# 02_-_USB.net
KiCad netlist of a schematic drawn in Altium Designer
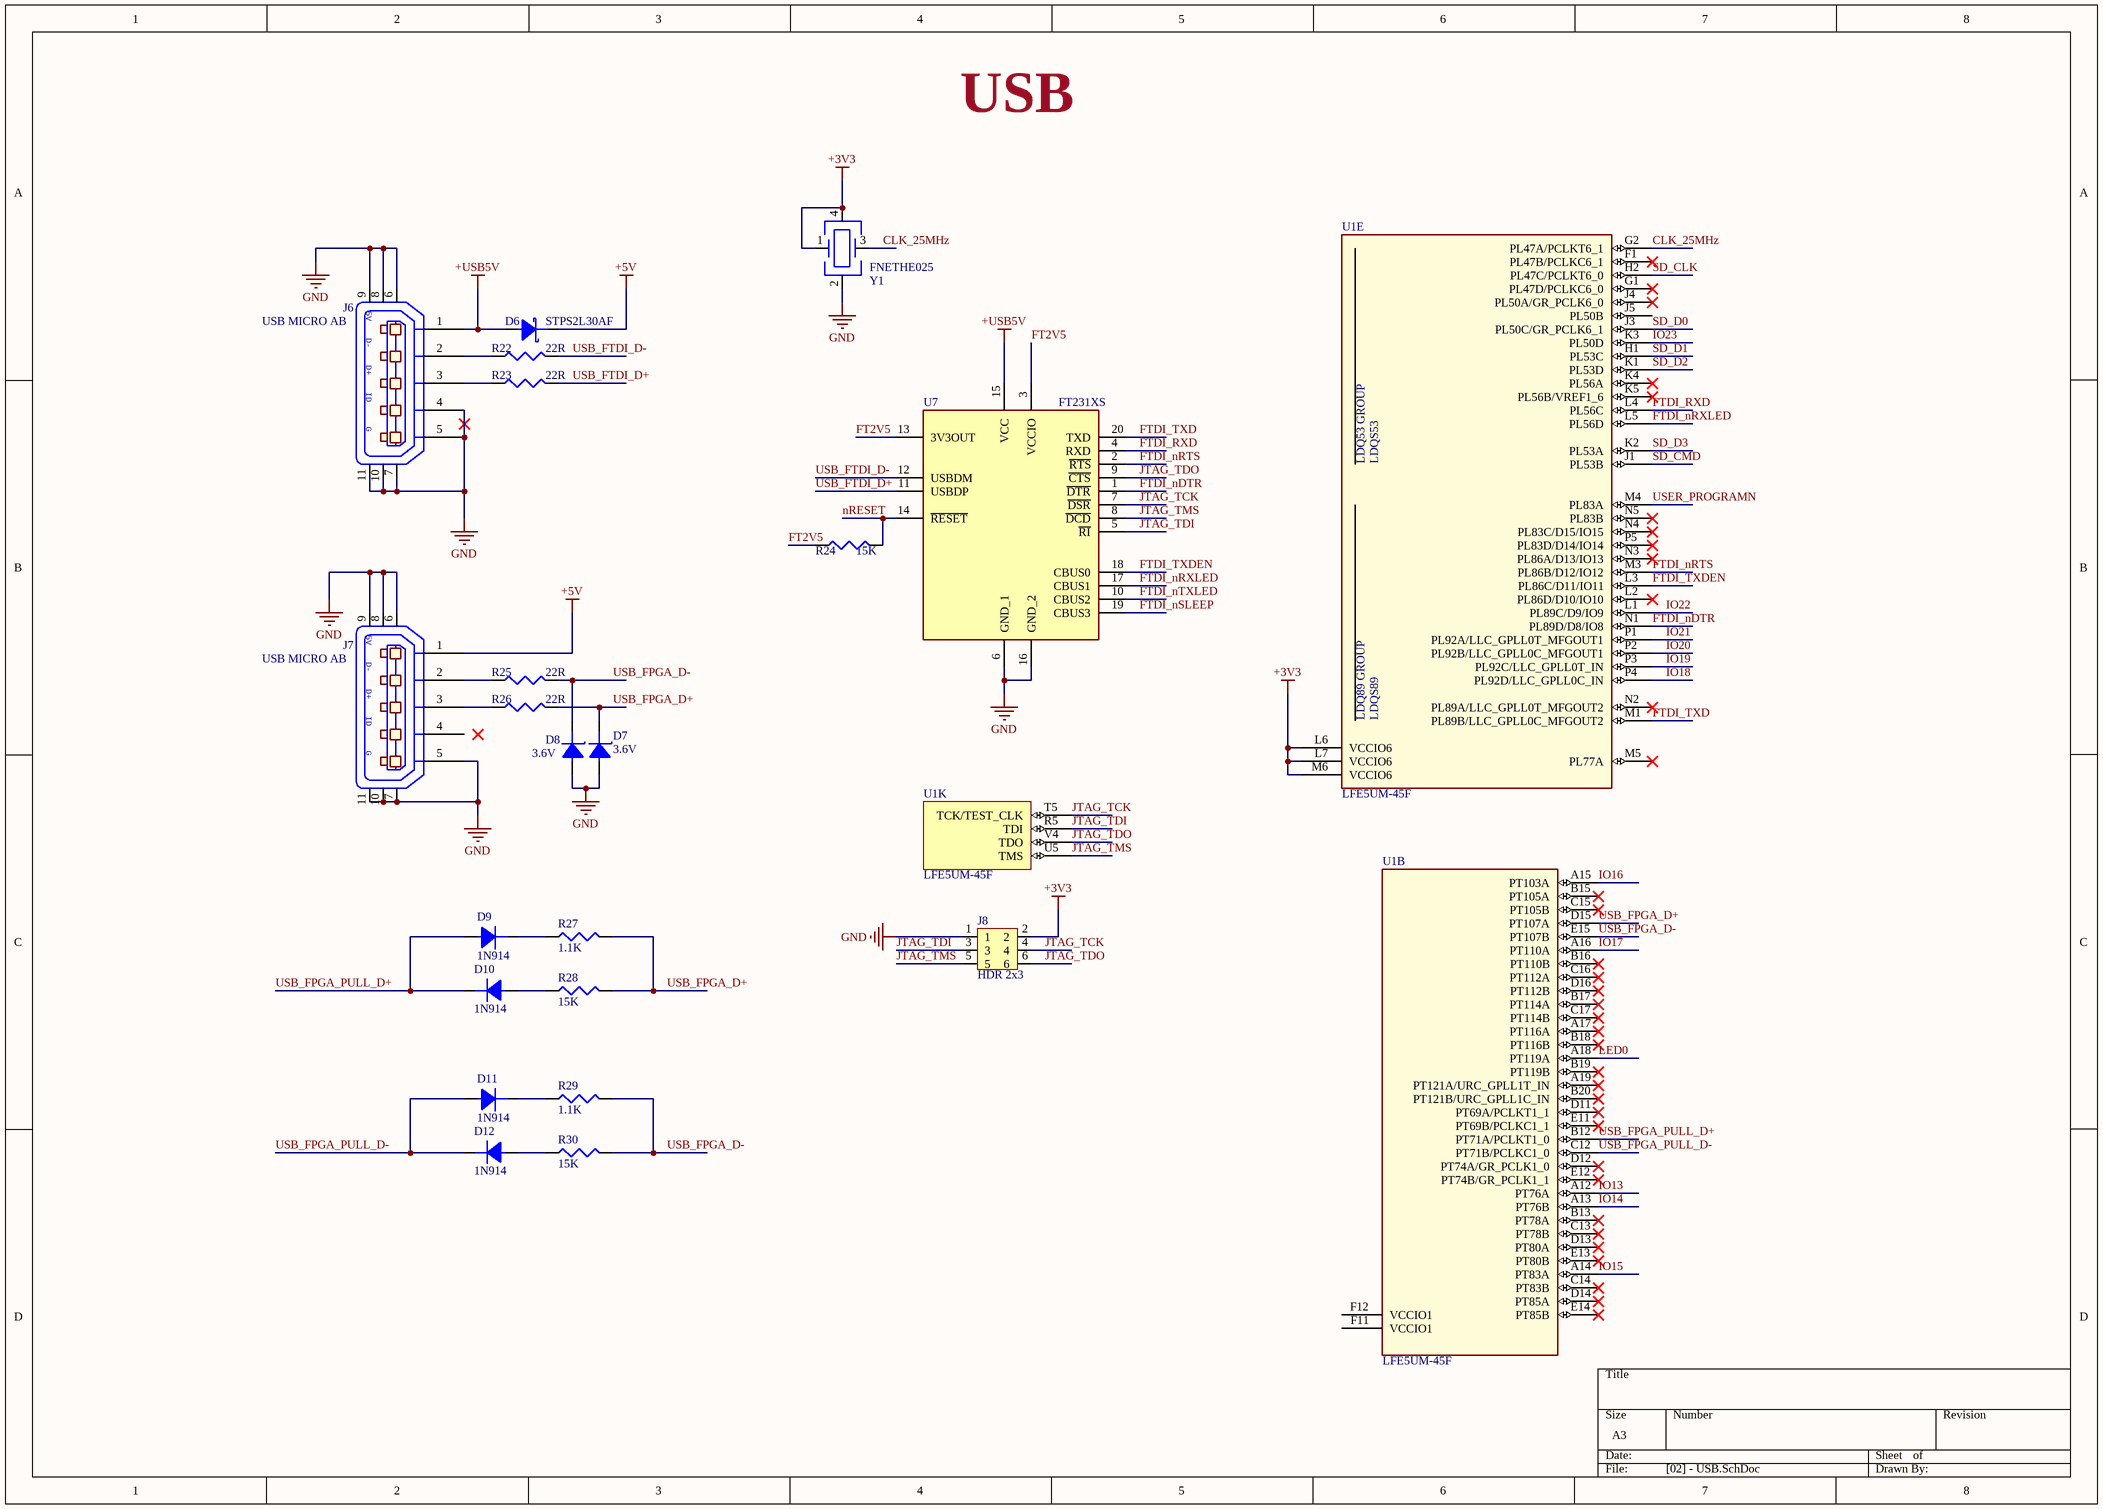
[diagram p0: [02] - USB.SchDoc]

(export (version "E")
  (design (tool "Eeschema 10.0.6"))
  (components
    (comp (ref "D6")
      (value "STPS2L30AF")
      (footprint "SMA")
      (description "DIODE SCHOTTKY 30V 2A SMA")
      (fields (field (name "MANUFACTURER") "STMicroelectronics"))
      (libsource (lib "ECP5_V2") (part "STPS2L30AF"))
    )
    (comp (ref "D7")
      (value "3.6V")
      (footprint "SOD323")
      (description "Diode Zener Single 3.6V 5% 200mW 2-Pin SOD-323 T/R")
      (fields (field (name "MANUFACTURER") "MCC") (field (name "MANUFACTURER PART NUMBER") "BZT52C3V6S-TP"))
      (libsource (lib "ECP5_V2") (part "BZT52C3V6S-TP"))
    )
    (comp (ref "D8")
      (value "3.6V")
      (footprint "SOD323")
      (description "Diode Zener Single 3.6V 5% 200mW 2-Pin SOD-323 T/R")
      (fields (field (name "MANUFACTURER") "MCC") (field (name "MANUFACTURER PART NUMBER") "BZT52C3V6S-TP"))
      (libsource (lib "ECP5_V2") (part "BZT52C3V6S-TP"))
    )
    (comp (ref "D9")
      (value "1N914")
      (footprint "SOD323")
      (description "ON SEMICONDUCTOR/FAIRCHILD - 1N914BWS. - SMALL SIGNAL DIODE")
      (fields
        (field (name "MANUFACTURER") "ON Semiconductor / Fairchild")
        (field (name "MANUFACTURER PART NUMBER") "1N914BWS")
      )
      (libsource (lib "ECP5_V2") (part "1N914BWS"))
    )
    (comp (ref "D10")
      (value "1N914")
      (footprint "SOD323")
      (description "ON SEMICONDUCTOR/FAIRCHILD - 1N914BWS. - SMALL SIGNAL DIODE")
      (fields
        (field (name "MANUFACTURER") "ON Semiconductor / Fairchild")
        (field (name "MANUFACTURER PART NUMBER") "1N914BWS")
      )
      (libsource (lib "ECP5_V2") (part "1N914BWS"))
    )
    (comp (ref "D11")
      (value "1N914")
      (footprint "SOD323")
      (description "ON SEMICONDUCTOR/FAIRCHILD - 1N914BWS. - SMALL SIGNAL DIODE")
      (fields
        (field (name "MANUFACTURER") "ON Semiconductor / Fairchild")
        (field (name "MANUFACTURER PART NUMBER") "1N914BWS")
      )
      (libsource (lib "ECP5_V2") (part "1N914BWS"))
    )
    (comp (ref "D12")
      (value "1N914")
      (footprint "SOD323")
      (description "ON SEMICONDUCTOR/FAIRCHILD - 1N914BWS. - SMALL SIGNAL DIODE")
      (fields
        (field (name "MANUFACTURER") "ON Semiconductor / Fairchild")
        (field (name "MANUFACTURER PART NUMBER") "1N914BWS")
      )
      (libsource (lib "ECP5_V2") (part "1N914BWS"))
    )
    (comp (ref "J6")
      (value "USB MICRO AB")
      (footprint "USB_Micro_AB")
      (description "CONN RCPT MICRO USB AB R/A SMD")
      (fields
        (field (name "MANUFACTURER") "Molex Inc")
        (field (name "MANUFACTURER PART NUMBER") "0475890001")
        (field (name ".CREATOR") "MM")
        (field (name ".CHECKED PCB") "MM")
        (field (name ".CHECKED SCH") "MM")
      )
      (libsource (lib "ECP5_V2") (part "0475890001"))
    )
    (comp (ref "J7")
      (value "USB MICRO AB")
      (footprint "USB_Micro_AB")
      (description "CONN RCPT MICRO USB AB R/A SMD")
      (fields
        (field (name "MANUFACTURER") "Molex Inc")
        (field (name "MANUFACTURER PART NUMBER") "0475890001")
        (field (name ".CREATOR") "MM")
        (field (name ".CHECKED PCB") "MM")
        (field (name ".CHECKED SCH") "MM")
      )
      (libsource (lib "ECP5_V2") (part "0475890001"))
    )
    (comp (ref "J8")
      (value "HDR 2x3")
      (footprint "HDR_2x3_2.54MM")
      (description "CONN HEADER VERT 6POS 2.54MM")
      (fields
        (field (name "MANUFACTURER") "Amphenol FCI")
        (field (name "MANUFACTURER PART NUMBER") "67997-106HLF")
      )
      (libsource (lib "ECP5_V2") (part "67997-106HLF"))
    )
    (comp (ref "R22")
      (value "22R")
      (footprint "R0603")
      (description "Res Thick Film 0603 22 Ohm 1% 0.1W(1/10W) ±100ppm/C Pad SMD T/R")
      (fields
        (field (name "MANUFACTURER") "Yageo")
        (field (name "MANUFACTURER PART NUMBER") "RC0603FR-0722RL")
      )
      (libsource (lib "ECP5_V2") (part "RC0603FR-0722RL"))
    )
    (comp (ref "R23")
      (value "22R")
      (footprint "R0603")
      (description "Res Thick Film 0603 22 Ohm 1% 0.1W(1/10W) ±100ppm/C Pad SMD T/R")
      (fields
        (field (name "MANUFACTURER") "Yageo")
        (field (name "MANUFACTURER PART NUMBER") "RC0603FR-0722RL")
      )
      (libsource (lib "ECP5_V2") (part "RC0603FR-0722RL"))
    )
    (comp (ref "R24")
      (value "15K")
      (footprint "R0603")
      (description "Res Thick Film 0603 15K Ohm 1% 1/10W ?100ppm/?C Molded SMD Paper T/R")
      (fields
        (field (name "MANUFACTURER") "Yageo")
        (field (name "MANUFACTURER PART NUMBER") "RC0603FR-0715KL")
      )
      (libsource (lib "ECP5_V2") (part "RC0603FR-0715KL"))
    )
    (comp (ref "R25")
      (value "22R")
      (footprint "R0603")
      (description "Res Thick Film 0603 22 Ohm 1% 0.1W(1/10W) ±100ppm/C Pad SMD T/R")
      (fields
        (field (name "MANUFACTURER") "Yageo")
        (field (name "MANUFACTURER PART NUMBER") "RC0603FR-0722RL")
      )
      (libsource (lib "ECP5_V2") (part "RC0603FR-0722RL"))
    )
    (comp (ref "R26")
      (value "22R")
      (footprint "R0603")
      (description "Res Thick Film 0603 22 Ohm 1% 0.1W(1/10W) ±100ppm/C Pad SMD T/R")
      (fields
        (field (name "MANUFACTURER") "Yageo")
        (field (name "MANUFACTURER PART NUMBER") "RC0603FR-0722RL")
      )
      (libsource (lib "ECP5_V2") (part "RC0603FR-0722RL"))
    )
    (comp (ref "R27")
      (value "1.1K")
      (footprint "R0603")
      (description "RES SMD 1.1K OHM 1% 1/10W 0603")
      (fields
        (field (name "MANUFACTURER") "Yageo")
        (field (name "MANUFACTURER PART NUMBER") "RC0603FR-071K1L")
      )
      (libsource (lib "ECP5_V2") (part "RC0603FR-071K1L"))
    )
    (comp (ref "R28")
      (value "15K")
      (footprint "R0603")
      (description "Res Thick Film 0603 15K Ohm 1% 1/10W ?100ppm/?C Molded SMD Paper T/R")
      (fields
        (field (name "MANUFACTURER") "Yageo")
        (field (name "MANUFACTURER PART NUMBER") "RC0603FR-0715KL")
      )
      (libsource (lib "ECP5_V2") (part "RC0603FR-0715KL"))
    )
    (comp (ref "R29")
      (value "1.1K")
      (footprint "R0603")
      (description "RES SMD 1.1K OHM 1% 1/10W 0603")
      (fields
        (field (name "MANUFACTURER") "Yageo")
        (field (name "MANUFACTURER PART NUMBER") "RC0603FR-071K1L")
      )
      (libsource (lib "ECP5_V2") (part "RC0603FR-071K1L"))
    )
    (comp (ref "R30")
      (value "15K")
      (footprint "R0603")
      (description "Res Thick Film 0603 15K Ohm 1% 1/10W ?100ppm/?C Molded SMD Paper T/R")
      (fields
        (field (name "MANUFACTURER") "Yageo")
        (field (name "MANUFACTURER PART NUMBER") "RC0603FR-0715KL")
      )
      (libsource (lib "ECP5_V2") (part "RC0603FR-0715KL"))
    )
    (comp (ref "U1")
      (value "LFE5UM-45F")
      (footprint "LFE5BG381")
      (description "ECP5 Series 44 K LUTs 203 I/O 1.1 V Slow Surface Mount FPGA - CABGA-381")
      (fields
        (field (name "MANUFACTURER") "Lattice Semiconductor")
        (field (name "MANUFACTURER PART NUMBER") "LFE5UM-45F-6BG381C")
      )
      (libsource (lib "ECP5_V2") (part "LFE5UM-45F-6BG381C"))
    )
    (comp (ref "U7")
      (value "FT231XS")
      (footprint "SOP64P599X175-20N")
      (fields (field (name "MANUFACTURER") "FTDI") (field (name "MANUFACTURER PART NUMBER") "FT231XS-R"))
      (libsource (lib "ECP5_V2") (part "FT231XS-R"))
    )
    (comp (ref "Y1")
      (value "FNETHE025")
      (footprint "TSOP440P690X140-4N")
      (description "SMD Crystal Oscillator 25MHz 3.3V 15pF 4-Pin CSMD")
      (fields (field (name "MANUFACTURER") "Diodes"))
      (libsource (lib "ECP5_V2") (part "FNETHE025"))
    )
  )
  (nets
    (net (code "1") (name "+3V3") (class "Default")
      (node (ref "J8") (pin "2") (pinfunction "2_2") (pintype "passive"))
      (node (ref "U1") (pin "L6") (pinfunction "VCCIO6_L6") (pintype "power_in"))
      (node (ref "U1") (pin "L7") (pinfunction "VCCIO6_L7") (pintype "power_in"))
      (node (ref "U1") (pin "M6") (pinfunction "VCCIO6_M6") (pintype "power_in"))
      (node (ref "Y1") (pin "1") (pintype "passive"))
      (node (ref "Y1") (pin "4") (pinfunction "4_4") (pintype "passive"))
    )
    (net (code "2") (name "+5V") (class "Default")
      (node (ref "D6") (pin "1") (pinfunction "Cathode_1") (pintype "passive"))
      (node (ref "J7") (pin "1") (pinfunction "P1_1") (pintype "passive"))
    )
    (net (code "3") (name "+USB5V") (class "Default")
      (node (ref "D6") (pin "2") (pinfunction "Anode_2") (pintype "passive"))
      (node (ref "J6") (pin "1") (pinfunction "P1_1") (pintype "passive"))
      (node (ref "U7") (pin "15") (pinfunction "VCC_15") (pintype "passive"))
    )
    (net (code "4") (name "/CLK_25MHz") (class "Default")
      (node (ref "U1") (pin "G2") (pinfunction "PL47A/PCLKT6_1_G2") (pintype "bidirectional"))
      (node (ref "Y1") (pin "3") (pinfunction "3_3") (pintype "passive"))
    )
    (net (code "5") (name "/FT2V5") (class "Default")
      (node (ref "R24") (pin "1") (pinfunction "1_1") (pintype "passive"))
      (node (ref "U7") (pin "13") (pinfunction "3V3OUT_13") (pintype "passive"))
      (node (ref "U7") (pin "3") (pinfunction "VCCIO_3") (pintype "passive"))
    )
    (net (code "6") (name "/FTDI_RXD") (class "Default")
      (node (ref "U1") (pin "L4") (pinfunction "PL56C_L4") (pintype "bidirectional"))
      (node (ref "U7") (pin "4") (pinfunction "RXD_4") (pintype "passive"))
    )
    (net (code "7") (name "/FTDI_TXD") (class "Default")
      (node (ref "U1") (pin "M1") (pinfunction "PL89B/LLC_GPLL0C_MFGOUT2_M1") (pintype "bidirectional"))
      (node (ref "U7") (pin "20") (pinfunction "TXD_20") (pintype "passive"))
    )
    (net (code "8") (name "/FTDI_TXDEN") (class "Default")
      (node (ref "U1") (pin "L3") (pinfunction "PL86C/D11/IO11_L3") (pintype "bidirectional"))
      (node (ref "U7") (pin "18") (pinfunction "CBUS0_18") (pintype "passive"))
    )
    (net (code "9") (name "/FTDI_nDTR") (class "Default")
      (node (ref "U1") (pin "N1") (pinfunction "PL89D/D8/IO8_N1") (pintype "bidirectional"))
      (node (ref "U7") (pin "1") (pinfunction "~{DTR}_1") (pintype "passive"))
    )
    (net (code "10") (name "/FTDI_nRTS") (class "Default")
      (node (ref "U1") (pin "M3") (pinfunction "PL86B/D12/IO12_M3") (pintype "bidirectional"))
      (node (ref "U7") (pin "2") (pinfunction "~{RTS}_2") (pintype "passive"))
    )
    (net (code "11") (name "/FTDI_nRXLED") (class "Default")
      (node (ref "U1") (pin "L5") (pinfunction "PL56D_L5") (pintype "bidirectional"))
      (node (ref "U7") (pin "17") (pinfunction "CBUS1_17") (pintype "passive"))
    )
    (net (code "12") (name "/FTDI_nSLEEP") (class "Default")
      (node (ref "U7") (pin "19") (pinfunction "CBUS3_19") (pintype "passive"))
    )
    (net (code "13") (name "/FTDI_nTXLED") (class "Default")
      (node (ref "U7") (pin "10") (pinfunction "CBUS2_10") (pintype "passive"))
    )
    (net (code "14") (name "/IO13") (class "Default")
      (node (ref "U1") (pin "A12") (pinfunction "PT76A_A12") (pintype "bidirectional"))
    )
    (net (code "15") (name "/IO14") (class "Default")
      (node (ref "U1") (pin "A13") (pinfunction "PT76B_A13") (pintype "bidirectional"))
    )
    (net (code "16") (name "/IO15") (class "Default")
      (node (ref "U1") (pin "A14") (pinfunction "PT83A_A14") (pintype "bidirectional"))
    )
    (net (code "17") (name "/IO16") (class "Default")
      (node (ref "U1") (pin "A15") (pinfunction "PT103A_A15") (pintype "bidirectional"))
    )
    (net (code "18") (name "/IO17") (class "Default")
      (node (ref "U1") (pin "A16") (pinfunction "PT110A_A16") (pintype "bidirectional"))
    )
    (net (code "19") (name "/IO18") (class "Default")
      (node (ref "U1") (pin "P4") (pinfunction "PL92D/LLC_GPLL0C_IN_P4") (pintype "bidirectional"))
    )
    (net (code "20") (name "/IO19") (class "Default")
      (node (ref "U1") (pin "P3") (pinfunction "PL92C/LLC_GPLL0T_IN_P3") (pintype "bidirectional"))
    )
    (net (code "21") (name "/IO20") (class "Default")
      (node (ref "U1") (pin "P2") (pinfunction "PL92B/LLC_GPLL0C_MFGOUT1_P2") (pintype "bidirectional"))
    )
    (net (code "22") (name "/IO21") (class "Default")
      (node (ref "U1") (pin "P1") (pinfunction "PL92A/LLC_GPLL0T_MFGOUT1_P1") (pintype "bidirectional"))
    )
    (net (code "23") (name "/IO22") (class "Default")
      (node (ref "U1") (pin "L1") (pinfunction "PL89C/D9/IO9_L1") (pintype "bidirectional"))
    )
    (net (code "24") (name "/IO23") (class "Default")
      (node (ref "U1") (pin "K3") (pinfunction "PL50D_K3") (pintype "bidirectional"))
    )
    (net (code "25") (name "/JTAG_TCK") (class "Default")
      (node (ref "J8") (pin "4") (pinfunction "4_4") (pintype "passive"))
      (node (ref "U1") (pin "T5") (pinfunction "TCK/TEST_CLK_T5") (pintype "bidirectional"))
      (node (ref "U7") (pin "7") (pinfunction "~{DSR}_7") (pintype "passive"))
    )
    (net (code "26") (name "/JTAG_TDI") (class "Default")
      (node (ref "J8") (pin "3") (pinfunction "3_3") (pintype "passive"))
      (node (ref "U1") (pin "R5") (pinfunction "TDI_R5") (pintype "bidirectional"))
      (node (ref "U7") (pin "5") (pinfunction "~{RI}_5") (pintype "passive"))
    )
    (net (code "27") (name "/JTAG_TDO") (class "Default")
      (node (ref "J8") (pin "6") (pinfunction "6_6") (pintype "passive"))
      (node (ref "U1") (pin "V4") (pinfunction "TDO_V4") (pintype "bidirectional"))
      (node (ref "U7") (pin "9") (pinfunction "~{CTS}_9") (pintype "passive"))
    )
    (net (code "28") (name "/JTAG_TMS") (class "Default")
      (node (ref "J8") (pin "5") (pinfunction "5_5") (pintype "passive"))
      (node (ref "U1") (pin "U5") (pinfunction "TMS_U5") (pintype "bidirectional"))
      (node (ref "U7") (pin "8") (pinfunction "~{DCD}_8") (pintype "passive"))
    )
    (net (code "29") (name "/LED0") (class "Default")
      (node (ref "U1") (pin "A18") (pinfunction "PT119A_A18") (pintype "bidirectional"))
    )
    (net (code "30") (name "/SD_CLK") (class "Default")
      (node (ref "U1") (pin "H2") (pinfunction "PL47C/PCLKT6_0_H2") (pintype "bidirectional"))
    )
    (net (code "31") (name "/SD_CMD") (class "Default")
      (node (ref "U1") (pin "J1") (pinfunction "PL53B_J1") (pintype "bidirectional"))
    )
    (net (code "32") (name "/SD_D0") (class "Default")
      (node (ref "U1") (pin "J3") (pinfunction "PL50C/GR_PCLK6_1_J3") (pintype "bidirectional"))
    )
    (net (code "33") (name "/SD_D1") (class "Default")
      (node (ref "U1") (pin "H1") (pinfunction "PL53C_H1") (pintype "bidirectional"))
    )
    (net (code "34") (name "/SD_D2") (class "Default")
      (node (ref "U1") (pin "K1") (pinfunction "PL53D_K1") (pintype "bidirectional"))
    )
    (net (code "35") (name "/SD_D3") (class "Default")
      (node (ref "U1") (pin "K2") (pinfunction "PL53A_K2") (pintype "bidirectional"))
    )
    (net (code "36") (name "/USB_FPGA_D+") (class "Default")
      (node (ref "D7") (pin "1") (pinfunction "Cathode_1") (pintype "passive"))
      (node (ref "R26") (pin "2") (pinfunction "2_2") (pintype "passive"))
      (node (ref "R27") (pin "2") (pinfunction "2_2") (pintype "passive"))
      (node (ref "R28") (pin "2") (pinfunction "2_2") (pintype "passive"))
      (node (ref "U1") (pin "D15") (pinfunction "PT107A_D15") (pintype "bidirectional"))
    )
    (net (code "37") (name "/USB_FPGA_D-") (class "Default")
      (node (ref "D8") (pin "1") (pinfunction "Cathode_1") (pintype "passive"))
      (node (ref "R25") (pin "2") (pinfunction "2_2") (pintype "passive"))
      (node (ref "R29") (pin "2") (pinfunction "2_2") (pintype "passive"))
      (node (ref "R30") (pin "2") (pinfunction "2_2") (pintype "passive"))
      (node (ref "U1") (pin "E15") (pinfunction "PT107B_E15") (pintype "bidirectional"))
    )
    (net (code "38") (name "/USB_FPGA_PULL_D+") (class "Default")
      (node (ref "D10") (pin "1") (pinfunction "Cathode_1") (pintype "passive"))
      (node (ref "D9") (pin "2") (pinfunction "Anode_2") (pintype "passive"))
      (node (ref "U1") (pin "B12") (pinfunction "PT71A/PCLKT1_0_B12") (pintype "bidirectional"))
    )
    (net (code "39") (name "/USB_FPGA_PULL_D-") (class "Default")
      (node (ref "D11") (pin "2") (pinfunction "Anode_2") (pintype "passive"))
      (node (ref "D12") (pin "1") (pinfunction "Cathode_1") (pintype "passive"))
      (node (ref "U1") (pin "C12") (pinfunction "PT71B/PCLKC1_0_C12") (pintype "bidirectional"))
    )
    (net (code "40") (name "/USB_FTDI_D+") (class "Default")
      (node (ref "R23") (pin "2") (pinfunction "2_2") (pintype "passive"))
      (node (ref "U7") (pin "11") (pinfunction "USBDP_11") (pintype "passive"))
    )
    (net (code "41") (name "/USB_FTDI_D-") (class "Default")
      (node (ref "R22") (pin "2") (pinfunction "2_2") (pintype "passive"))
      (node (ref "U7") (pin "12") (pinfunction "USBDM_12") (pintype "passive"))
    )
    (net (code "42") (name "/USER_PROGRAMN") (class "Default")
      (node (ref "U1") (pin "M4") (pinfunction "PL83A_M4") (pintype "bidirectional"))
    )
    (net (code "43") (name "/nRESET") (class "Default")
      (node (ref "R24") (pin "2") (pinfunction "2_2") (pintype "passive"))
      (node (ref "U7") (pin "14") (pinfunction "~{RESET}_14") (pintype "passive"))
    )
    (net (code "44") (name "GND") (class "Default")
      (node (ref "D7") (pin "2") (pinfunction "Anode_2") (pintype "passive"))
      (node (ref "D8") (pin "2") (pinfunction "Anode_2") (pintype "passive"))
      (node (ref "J6") (pin "10") (pinfunction "10_10") (pintype "passive"))
      (node (ref "J6") (pin "11") (pinfunction "11_11") (pintype "passive"))
      (node (ref "J6") (pin "4") (pinfunction "P4_4") (pintype "passive"))
      (node (ref "J6") (pin "5") (pinfunction "P5_5") (pintype "passive"))
      (node (ref "J6") (pin "6") (pinfunction "6_6") (pintype "passive"))
      (node (ref "J6") (pin "7") (pinfunction "7_7") (pintype "passive"))
      (node (ref "J6") (pin "8") (pinfunction "8_8") (pintype "passive"))
      (node (ref "J6") (pin "9") (pinfunction "9_9") (pintype "passive"))
      (node (ref "J7") (pin "10") (pinfunction "10_10") (pintype "passive"))
      (node (ref "J7") (pin "11") (pinfunction "11_11") (pintype "passive"))
      (node (ref "J7") (pin "5") (pinfunction "P5_5") (pintype "passive"))
      (node (ref "J7") (pin "6") (pinfunction "6_6") (pintype "passive"))
      (node (ref "J7") (pin "7") (pinfunction "7_7") (pintype "passive"))
      (node (ref "J7") (pin "8") (pinfunction "8_8") (pintype "passive"))
      (node (ref "J7") (pin "9") (pinfunction "9_9") (pintype "passive"))
      (node (ref "J8") (pin "1") (pinfunction "1_1") (pintype "passive"))
      (node (ref "U7") (pin "16") (pinfunction "GND_2_16") (pintype "passive"))
      (node (ref "U7") (pin "6") (pinfunction "GND_1_6") (pintype "passive"))
      (node (ref "Y1") (pin "2") (pinfunction "2_2") (pintype "passive"))
    )
    (net (code "45") (name "Net-(D9-Cathode)") (class "Default")
      (node (ref "D9") (pin "1") (pinfunction "Cathode_1") (pintype "passive"))
      (node (ref "R27") (pin "1") (pinfunction "1_1") (pintype "passive"))
    )
    (net (code "46") (name "Net-(D10-Anode)") (class "Default")
      (node (ref "D10") (pin "2") (pinfunction "Anode_2") (pintype "passive"))
      (node (ref "R28") (pin "1") (pinfunction "1_1") (pintype "passive"))
    )
    (net (code "47") (name "Net-(D11-Cathode)") (class "Default")
      (node (ref "D11") (pin "1") (pinfunction "Cathode_1") (pintype "passive"))
      (node (ref "R29") (pin "1") (pinfunction "1_1") (pintype "passive"))
    )
    (net (code "48") (name "Net-(D12-Anode)") (class "Default")
      (node (ref "D12") (pin "2") (pinfunction "Anode_2") (pintype "passive"))
      (node (ref "R30") (pin "1") (pinfunction "1_1") (pintype "passive"))
    )
    (net (code "49") (name "Net-(J6-P2)") (class "Default")
      (node (ref "J6") (pin "2") (pinfunction "P2_2") (pintype "passive"))
      (node (ref "R22") (pin "1") (pinfunction "1_1") (pintype "passive"))
    )
    (net (code "50") (name "Net-(J6-P3)") (class "Default")
      (node (ref "J6") (pin "3") (pinfunction "P3_3") (pintype "passive"))
      (node (ref "R23") (pin "1") (pinfunction "1_1") (pintype "passive"))
    )
    (net (code "51") (name "Net-(J7-P2)") (class "Default")
      (node (ref "J7") (pin "2") (pinfunction "P2_2") (pintype "passive"))
      (node (ref "R25") (pin "1") (pinfunction "1_1") (pintype "passive"))
    )
    (net (code "52") (name "Net-(J7-P3)") (class "Default")
      (node (ref "J7") (pin "3") (pinfunction "P3_3") (pintype "passive"))
      (node (ref "R26") (pin "1") (pinfunction "1_1") (pintype "passive"))
    )
    (net (code "53") (name "unconnected-(J7-P4-Pad4)") (class "Default")
      (node (ref "J7") (pin "4") (pinfunction "P4_4") (pintype "passive"))
    )
    (net (code "54") (name "unconnected-(U1B-PT69A{slash}PCLKT1_1-PadD11)") (class "Default")
      (node (ref "U1") (pin "D11") (pinfunction "PT69A/PCLKT1_1_D11") (pintype "bidirectional+no_connect"))
    )
    (net (code "55") (name "unconnected-(U1B-PT69B{slash}PCLKC1_1-PadE11)") (class "Default")
      (node (ref "U1") (pin "E11") (pinfunction "PT69B/PCLKC1_1_E11") (pintype "bidirectional+no_connect"))
    )
    (net (code "56") (name "unconnected-(U1B-PT74A{slash}GR_PCLK1_0-PadD12)") (class "Default")
      (node (ref "U1") (pin "D12") (pinfunction "PT74A/GR_PCLK1_0_D12") (pintype "bidirectional+no_connect"))
    )
    (net (code "57") (name "unconnected-(U1B-PT74B{slash}GR_PCLK1_1-PadE12)") (class "Default")
      (node (ref "U1") (pin "E12") (pinfunction "PT74B/GR_PCLK1_1_E12") (pintype "bidirectional+no_connect"))
    )
    (net (code "58") (name "unconnected-(U1B-PT78A-PadB13)") (class "Default")
      (node (ref "U1") (pin "B13") (pinfunction "PT78A_B13") (pintype "bidirectional+no_connect"))
    )
    (net (code "59") (name "unconnected-(U1B-PT78B-PadC13)") (class "Default")
      (node (ref "U1") (pin "C13") (pinfunction "PT78B_C13") (pintype "bidirectional+no_connect"))
    )
    (net (code "60") (name "unconnected-(U1B-PT80A-PadD13)") (class "Default")
      (node (ref "U1") (pin "D13") (pinfunction "PT80A_D13") (pintype "bidirectional+no_connect"))
    )
    (net (code "61") (name "unconnected-(U1B-PT80B-PadE13)") (class "Default")
      (node (ref "U1") (pin "E13") (pinfunction "PT80B_E13") (pintype "bidirectional+no_connect"))
    )
    (net (code "62") (name "unconnected-(U1B-PT83B-PadC14)") (class "Default")
      (node (ref "U1") (pin "C14") (pinfunction "PT83B_C14") (pintype "bidirectional+no_connect"))
    )
    (net (code "63") (name "unconnected-(U1B-PT85A-PadD14)") (class "Default")
      (node (ref "U1") (pin "D14") (pinfunction "PT85A_D14") (pintype "bidirectional+no_connect"))
    )
    (net (code "64") (name "unconnected-(U1B-PT85B-PadE14)") (class "Default")
      (node (ref "U1") (pin "E14") (pinfunction "PT85B_E14") (pintype "bidirectional+no_connect"))
    )
    (net (code "65") (name "unconnected-(U1B-PT105A-PadB15)") (class "Default")
      (node (ref "U1") (pin "B15") (pinfunction "PT105A_B15") (pintype "bidirectional+no_connect"))
    )
    (net (code "66") (name "unconnected-(U1B-PT105B-PadC15)") (class "Default")
      (node (ref "U1") (pin "C15") (pinfunction "PT105B_C15") (pintype "bidirectional+no_connect"))
    )
    (net (code "67") (name "unconnected-(U1B-PT110B-PadB16)") (class "Default")
      (node (ref "U1") (pin "B16") (pinfunction "PT110B_B16") (pintype "bidirectional+no_connect"))
    )
    (net (code "68") (name "unconnected-(U1B-PT112A-PadC16)") (class "Default")
      (node (ref "U1") (pin "C16") (pinfunction "PT112A_C16") (pintype "bidirectional+no_connect"))
    )
    (net (code "69") (name "unconnected-(U1B-PT112B-PadD16)") (class "Default")
      (node (ref "U1") (pin "D16") (pinfunction "PT112B_D16") (pintype "bidirectional+no_connect"))
    )
    (net (code "70") (name "unconnected-(U1B-PT114A-PadB17)") (class "Default")
      (node (ref "U1") (pin "B17") (pinfunction "PT114A_B17") (pintype "bidirectional+no_connect"))
    )
    (net (code "71") (name "unconnected-(U1B-PT114B-PadC17)") (class "Default")
      (node (ref "U1") (pin "C17") (pinfunction "PT114B_C17") (pintype "bidirectional+no_connect"))
    )
    (net (code "72") (name "unconnected-(U1B-PT116A-PadA17)") (class "Default")
      (node (ref "U1") (pin "A17") (pinfunction "PT116A_A17") (pintype "bidirectional+no_connect"))
    )
    (net (code "73") (name "unconnected-(U1B-PT116B-PadB18)") (class "Default")
      (node (ref "U1") (pin "B18") (pinfunction "PT116B_B18") (pintype "bidirectional+no_connect"))
    )
    (net (code "74") (name "unconnected-(U1B-PT119B-PadB19)") (class "Default")
      (node (ref "U1") (pin "B19") (pinfunction "PT119B_B19") (pintype "bidirectional+no_connect"))
    )
    (net (code "75") (name "unconnected-(U1B-PT121A{slash}URC_GPLL1T_IN-PadA19)") (class "Default")
      (node (ref "U1") (pin "A19") (pinfunction "PT121A/URC_GPLL1T_IN_A19") (pintype "bidirectional+no_connect"))
    )
    (net (code "76") (name "unconnected-(U1B-PT121B{slash}URC_GPLL1C_IN-PadB20)") (class "Default")
      (node (ref "U1") (pin "B20") (pinfunction "PT121B/URC_GPLL1C_IN_B20") (pintype "bidirectional+no_connect"))
    )
    (net (code "77") (name "unconnected-(U1B-VCCIO1-PadF11)") (class "Default")
      (node (ref "U1") (pin "F11") (pinfunction "VCCIO1_F11") (pintype "power_in"))
    )
    (net (code "78") (name "unconnected-(U1B-VCCIO1-PadF12)") (class "Default")
      (node (ref "U1") (pin "F12") (pinfunction "VCCIO1_F12") (pintype "power_in"))
    )
    (net (code "79") (name "unconnected-(U1E-PL47B{slash}PCLKC6_1-PadF1)") (class "Default")
      (node (ref "U1") (pin "F1") (pinfunction "PL47B/PCLKC6_1_F1") (pintype "bidirectional+no_connect"))
    )
    (net (code "80") (name "unconnected-(U1E-PL47D{slash}PCLKC6_0-PadG1)") (class "Default")
      (node (ref "U1") (pin "G1") (pinfunction "PL47D/PCLKC6_0_G1") (pintype "bidirectional+no_connect"))
    )
    (net (code "81") (name "unconnected-(U1E-PL50A{slash}GR_PCLK6_0-PadJ4)") (class "Default")
      (node (ref "U1") (pin "J4") (pinfunction "PL50A/GR_PCLK6_0_J4") (pintype "bidirectional+no_connect"))
    )
    (net (code "82") (name "unconnected-(U1E-PL50B-PadJ5)") (class "Default")
      (node (ref "U1") (pin "J5") (pinfunction "PL50B_J5") (pintype "bidirectional"))
    )
    (net (code "83") (name "unconnected-(U1E-PL56A-PadK4)") (class "Default")
      (node (ref "U1") (pin "K4") (pinfunction "PL56A_K4") (pintype "bidirectional+no_connect"))
    )
    (net (code "84") (name "unconnected-(U1E-PL56B{slash}VREF1_6-PadK5)") (class "Default")
      (node (ref "U1") (pin "K5") (pinfunction "PL56B/VREF1_6_K5") (pintype "bidirectional+no_connect"))
    )
    (net (code "85") (name "unconnected-(U1E-PL77A-PadM5)") (class "Default")
      (node (ref "U1") (pin "M5") (pinfunction "PL77A_M5") (pintype "bidirectional+no_connect"))
    )
    (net (code "86") (name "unconnected-(U1E-PL83B-PadN5)") (class "Default")
      (node (ref "U1") (pin "N5") (pinfunction "PL83B_N5") (pintype "bidirectional+no_connect"))
    )
    (net (code "87") (name "unconnected-(U1E-PL83C{slash}D15{slash}IO15-PadN4)") (class "Default")
      (node (ref "U1") (pin "N4") (pinfunction "PL83C/D15/IO15_N4") (pintype "bidirectional+no_connect"))
    )
    (net (code "88") (name "unconnected-(U1E-PL83D{slash}D14{slash}IO14-PadP5)") (class "Default")
      (node (ref "U1") (pin "P5") (pinfunction "PL83D/D14/IO14_P5") (pintype "bidirectional+no_connect"))
    )
    (net (code "89") (name "unconnected-(U1E-PL86A{slash}D13{slash}IO13-PadN3)") (class "Default")
      (node (ref "U1") (pin "N3") (pinfunction "PL86A/D13/IO13_N3") (pintype "bidirectional+no_connect"))
    )
    (net (code "90") (name "unconnected-(U1E-PL86D{slash}D10{slash}IO10-PadL2)") (class "Default")
      (node (ref "U1") (pin "L2") (pinfunction "PL86D/D10/IO10_L2") (pintype "bidirectional+no_connect"))
    )
    (net (code "91") (name "unconnected-(U1E-PL89A{slash}LLC_GPLL0T_MFGOUT2-PadN2)") (class "Default")
      (node (ref "U1") (pin "N2") (pinfunction "PL89A/LLC_GPLL0T_MFGOUT2_N2") (pintype "bidirectional+no_connect"))
    )
  )
)
